# MOD_PWR_SW_CHM.net
KiCad netlist of a schematic drawn in Altium Designer
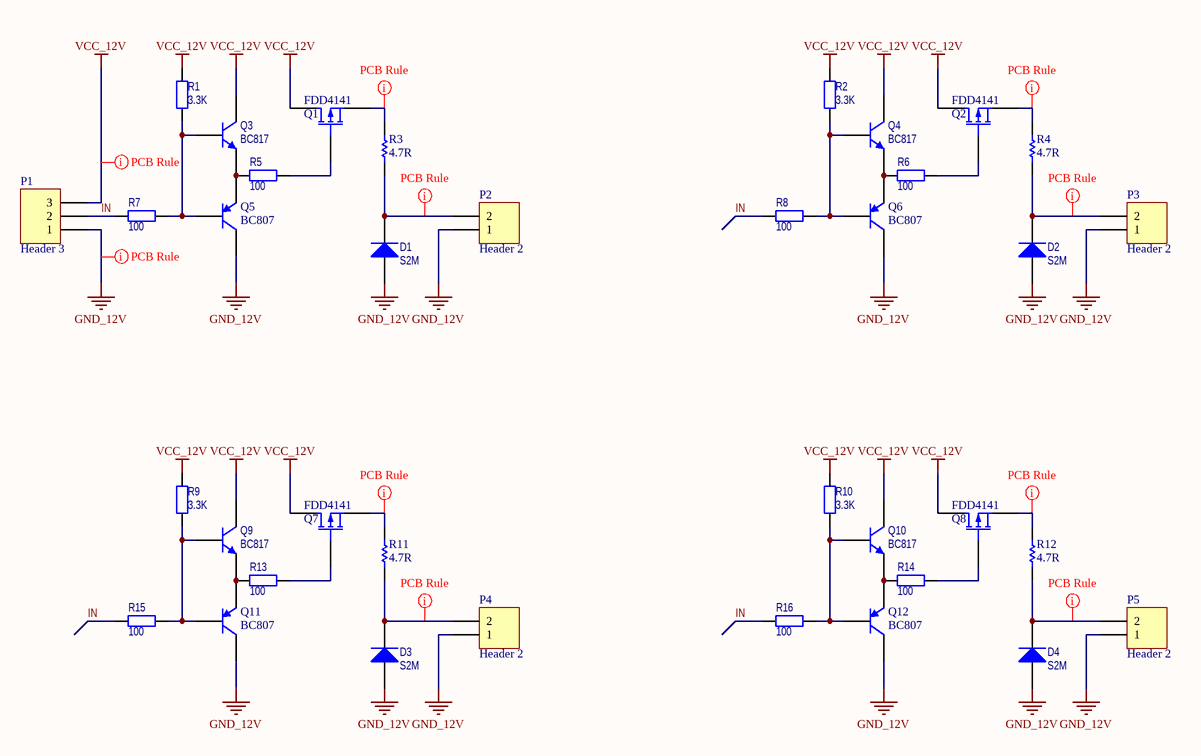
[diagram p0: MOD_PWR_SW_CHM.SchDoc]

(export (version "E")
  (design (tool "Eeschema 10.0.6"))
  (components
    (comp (ref "D1")
      (value "S2M")
      (footprint "SMB")
      (description "Default Diode")
      (fields (field (name "PUBLISHER") "Altium Limited"))
      (libsource (lib "Miscellaneous Devices") (part "Diode"))
    )
    (comp (ref "D2")
      (value "S2M")
      (footprint "SMB")
      (description "Default Diode")
      (fields (field (name "PUBLISHER") "Altium Limited"))
      (libsource (lib "Miscellaneous Devices") (part "Diode"))
    )
    (comp (ref "D3")
      (value "S2M")
      (footprint "SMB")
      (description "Default Diode")
      (fields (field (name "PUBLISHER") "Altium Limited"))
      (libsource (lib "Miscellaneous Devices") (part "Diode"))
    )
    (comp (ref "D4")
      (value "S2M")
      (footprint "SMB")
      (description "Default Diode")
      (fields (field (name "PUBLISHER") "Altium Limited"))
      (libsource (lib "Miscellaneous Devices") (part "Diode"))
    )
    (comp (ref "P1")
      (value "Header 3")
      (footprint "HDR1X3")
      (description "Header, 3-Pin")
      (fields (field (name "PUBLISHER") "Altium Limited"))
      (libsource (lib "Miscellaneous Connectors") (part "Header 3"))
    )
    (comp (ref "P2")
      (value "Header 2")
      (footprint "DG390-5.0:PCBComponent_1")
      (description "Header, 2-Pin")
      (fields (field (name "PUBLISHER") "Altium Limited"))
      (libsource (lib "Miscellaneous Connectors") (part "Header 2"))
    )
    (comp (ref "P3")
      (value "Header 2")
      (footprint "DG390-5.0:PCBComponent_1")
      (description "Header, 2-Pin")
      (fields (field (name "PUBLISHER") "Altium Limited"))
      (libsource (lib "Miscellaneous Connectors") (part "Header 2"))
    )
    (comp (ref "P4")
      (value "Header 2")
      (footprint "DG390-5.0:PCBComponent_1")
      (description "Header, 2-Pin")
      (fields (field (name "PUBLISHER") "Altium Limited"))
      (libsource (lib "Miscellaneous Connectors") (part "Header 2"))
    )
    (comp (ref "P5")
      (value "Header 2")
      (footprint "DG390-5.0:PCBComponent_1")
      (description "Header, 2-Pin")
      (fields (field (name "PUBLISHER") "Altium Limited"))
      (libsource (lib "Miscellaneous Connectors") (part "Header 2"))
    )
    (comp (ref "Q1")
      (value "FDD4141")
      (footprint "TO-252")
      (description "P-Channel MOSFET")
      (fields (field (name "PUBLISHER") "Altium Limited"))
      (libsource (lib "Miscellaneous Devices") (part "MOSFET-P"))
    )
    (comp (ref "Q2")
      (value "FDD4141")
      (footprint "TO-252")
      (description "P-Channel MOSFET")
      (fields (field (name "PUBLISHER") "Altium Limited"))
      (libsource (lib "Miscellaneous Devices") (part "MOSFET-P"))
    )
    (comp (ref "Q3")
      (value "BC817")
      (footprint "SOT23_M")
      (description "NPN Bipolar Transistor")
      (fields (field (name "PUBLISHER") "Altium Limited"))
      (libsource (lib "Miscellaneous Devices") (part "QNPN"))
    )
    (comp (ref "Q4")
      (value "BC817")
      (footprint "SOT23_M")
      (description "NPN Bipolar Transistor")
      (fields (field (name "PUBLISHER") "Altium Limited"))
      (libsource (lib "Miscellaneous Devices") (part "QNPN"))
    )
    (comp (ref "Q5")
      (value "BC807")
      (footprint "SOT23_M")
      (description "PNP General Purpose Amplifier")
      (fields (field (name "PUBLISHER") "Altium Limited"))
      (libsource (lib "Miscellaneous Devices") (part "2N3906"))
    )
    (comp (ref "Q6")
      (value "BC807")
      (footprint "SOT23_M")
      (description "PNP General Purpose Amplifier")
      (fields (field (name "PUBLISHER") "Altium Limited"))
      (libsource (lib "Miscellaneous Devices") (part "2N3906"))
    )
    (comp (ref "Q7")
      (value "FDD4141")
      (footprint "TO-252")
      (description "P-Channel MOSFET")
      (fields (field (name "PUBLISHER") "Altium Limited"))
      (libsource (lib "Miscellaneous Devices") (part "MOSFET-P"))
    )
    (comp (ref "Q8")
      (value "FDD4141")
      (footprint "TO-252")
      (description "P-Channel MOSFET")
      (fields (field (name "PUBLISHER") "Altium Limited"))
      (libsource (lib "Miscellaneous Devices") (part "MOSFET-P"))
    )
    (comp (ref "Q9")
      (value "BC817")
      (footprint "SOT23_M")
      (description "NPN Bipolar Transistor")
      (fields (field (name "PUBLISHER") "Altium Limited"))
      (libsource (lib "Miscellaneous Devices") (part "QNPN"))
    )
    (comp (ref "Q10")
      (value "BC817")
      (footprint "SOT23_M")
      (description "NPN Bipolar Transistor")
      (fields (field (name "PUBLISHER") "Altium Limited"))
      (libsource (lib "Miscellaneous Devices") (part "QNPN"))
    )
    (comp (ref "Q11")
      (value "BC807")
      (footprint "SOT23_M")
      (description "PNP General Purpose Amplifier")
      (fields (field (name "PUBLISHER") "Altium Limited"))
      (libsource (lib "Miscellaneous Devices") (part "2N3906"))
    )
    (comp (ref "Q12")
      (value "BC807")
      (footprint "SOT23_M")
      (description "PNP General Purpose Amplifier")
      (fields (field (name "PUBLISHER") "Altium Limited"))
      (libsource (lib "Miscellaneous Devices") (part "2N3906"))
    )
    (comp (ref "R1")
      (value "3.3K")
      (footprint "6-0805_N")
      (description "Resistor")
      (fields (field (name "Comment") "Res2") (field (name "PUBLISHER") "Altium Limited"))
      (libsource (lib "Miscellaneous Devices") (part "Res2"))
    )
    (comp (ref "R2")
      (value "3.3K")
      (footprint "6-0805_N")
      (description "Resistor")
      (fields (field (name "Comment") "Res2") (field (name "PUBLISHER") "Altium Limited"))
      (libsource (lib "Miscellaneous Devices") (part "Res2"))
    )
    (comp (ref "R3")
      (value "4.7R")
      (footprint "RES10W:PCBComponent_1")
      (description "Resistor")
      (fields (field (name "Comment") "Res1") (field (name "PUBLISHER") "Altium Limited"))
      (libsource (lib "Miscellaneous Devices") (part "Res1"))
    )
    (comp (ref "R4")
      (value "4.7R")
      (footprint "RES10W:PCBComponent_1")
      (description "Resistor")
      (fields (field (name "Comment") "Res1") (field (name "PUBLISHER") "Altium Limited"))
      (libsource (lib "Miscellaneous Devices") (part "Res1"))
    )
    (comp (ref "R5")
      (value "100")
      (footprint "6-0805_N")
      (description "Resistor")
      (fields (field (name "Comment") "Res2") (field (name "PUBLISHER") "Altium Limited"))
      (libsource (lib "") (part "Res2_1"))
    )
    (comp (ref "R6")
      (value "100")
      (footprint "6-0805_N")
      (description "Resistor")
      (fields (field (name "Comment") "Res2") (field (name "PUBLISHER") "Altium Limited"))
      (libsource (lib "") (part "Res2_1"))
    )
    (comp (ref "R7")
      (value "100")
      (footprint "6-0805_N")
      (description "Resistor")
      (fields (field (name "Comment") "Res2") (field (name "PUBLISHER") "Altium Limited"))
      (libsource (lib "") (part "Res2_1"))
    )
    (comp (ref "R8")
      (value "100")
      (footprint "6-0805_N")
      (description "Resistor")
      (fields (field (name "Comment") "Res2") (field (name "PUBLISHER") "Altium Limited"))
      (libsource (lib "") (part "Res2_1"))
    )
    (comp (ref "R9")
      (value "3.3K")
      (footprint "6-0805_N")
      (description "Resistor")
      (fields (field (name "Comment") "Res2") (field (name "PUBLISHER") "Altium Limited"))
      (libsource (lib "Miscellaneous Devices") (part "Res2"))
    )
    (comp (ref "R10")
      (value "3.3K")
      (footprint "6-0805_N")
      (description "Resistor")
      (fields (field (name "Comment") "Res2") (field (name "PUBLISHER") "Altium Limited"))
      (libsource (lib "Miscellaneous Devices") (part "Res2"))
    )
    (comp (ref "R11")
      (value "4.7R")
      (footprint "RES10W:PCBComponent_1")
      (description "Resistor")
      (fields (field (name "Comment") "Res1") (field (name "PUBLISHER") "Altium Limited"))
      (libsource (lib "Miscellaneous Devices") (part "Res1"))
    )
    (comp (ref "R12")
      (value "4.7R")
      (footprint "RES10W:PCBComponent_1")
      (description "Resistor")
      (fields (field (name "Comment") "Res1") (field (name "PUBLISHER") "Altium Limited"))
      (libsource (lib "Miscellaneous Devices") (part "Res1"))
    )
    (comp (ref "R13")
      (value "100")
      (footprint "6-0805_N")
      (description "Resistor")
      (fields (field (name "Comment") "Res2") (field (name "PUBLISHER") "Altium Limited"))
      (libsource (lib "") (part "Res2_1"))
    )
    (comp (ref "R14")
      (value "100")
      (footprint "6-0805_N")
      (description "Resistor")
      (fields (field (name "Comment") "Res2") (field (name "PUBLISHER") "Altium Limited"))
      (libsource (lib "") (part "Res2_1"))
    )
    (comp (ref "R15")
      (value "100")
      (footprint "6-0805_N")
      (description "Resistor")
      (fields (field (name "Comment") "Res2") (field (name "PUBLISHER") "Altium Limited"))
      (libsource (lib "") (part "Res2_1"))
    )
    (comp (ref "R16")
      (value "100")
      (footprint "6-0805_N")
      (description "Resistor")
      (fields (field (name "Comment") "Res2") (field (name "PUBLISHER") "Altium Limited"))
      (libsource (lib "") (part "Res2_1"))
    )
  )
  (nets
    (net (code "1") (name "/IN") (class "Default")
      (node (ref "P1") (pin "2") (pinfunction "2_2") (pintype "passive"))
      (node (ref "R15") (pin "2") (pinfunction "2_2") (pintype "passive"))
      (node (ref "R16") (pin "2") (pinfunction "2_2") (pintype "passive"))
      (node (ref "R7") (pin "2") (pinfunction "2_2") (pintype "passive"))
      (node (ref "R8") (pin "2") (pinfunction "2_2") (pintype "passive"))
    )
    (net (code "2") (name "GND_12V") (class "Default")
      (node (ref "D1") (pin "1") (pinfunction "A_1") (pintype "passive"))
      (node (ref "D2") (pin "1") (pinfunction "A_1") (pintype "passive"))
      (node (ref "D3") (pin "1") (pinfunction "A_1") (pintype "passive"))
      (node (ref "D4") (pin "1") (pinfunction "A_1") (pintype "passive"))
      (node (ref "P1") (pin "1") (pinfunction "1_1") (pintype "passive"))
      (node (ref "P2") (pin "1") (pinfunction "1_1") (pintype "passive"))
      (node (ref "P3") (pin "1") (pinfunction "1_1") (pintype "passive"))
      (node (ref "P4") (pin "1") (pinfunction "1_1") (pintype "passive"))
      (node (ref "P5") (pin "1") (pinfunction "1_1") (pintype "passive"))
      (node (ref "Q11") (pin "3") (pinfunction "C_3") (pintype "passive"))
      (node (ref "Q12") (pin "3") (pinfunction "C_3") (pintype "passive"))
      (node (ref "Q5") (pin "3") (pinfunction "C_3") (pintype "passive"))
      (node (ref "Q6") (pin "3") (pinfunction "C_3") (pintype "passive"))
    )
    (net (code "3") (name "Net-(D1-K)") (class "Default")
      (node (ref "D1") (pin "2") (pinfunction "K_2") (pintype "passive"))
      (node (ref "P2") (pin "2") (pinfunction "2_2") (pintype "passive"))
      (node (ref "R3") (pin "1") (pinfunction "1_1") (pintype "passive"))
    )
    (net (code "4") (name "Net-(D2-K)") (class "Default")
      (node (ref "D2") (pin "2") (pinfunction "K_2") (pintype "passive"))
      (node (ref "P3") (pin "2") (pinfunction "2_2") (pintype "passive"))
      (node (ref "R4") (pin "1") (pinfunction "1_1") (pintype "passive"))
    )
    (net (code "5") (name "Net-(D3-K)") (class "Default")
      (node (ref "D3") (pin "2") (pinfunction "K_2") (pintype "passive"))
      (node (ref "P4") (pin "2") (pinfunction "2_2") (pintype "passive"))
      (node (ref "R11") (pin "1") (pinfunction "1_1") (pintype "passive"))
    )
    (net (code "6") (name "Net-(D4-K)") (class "Default")
      (node (ref "D4") (pin "2") (pinfunction "K_2") (pintype "passive"))
      (node (ref "P5") (pin "2") (pinfunction "2_2") (pintype "passive"))
      (node (ref "R12") (pin "1") (pinfunction "1_1") (pintype "passive"))
    )
    (net (code "7") (name "Net-(Q1-G)") (class "Default")
      (node (ref "Q1") (pin "2") (pinfunction "G_2") (pintype "passive"))
      (node (ref "R5") (pin "1") (pinfunction "1_1") (pintype "passive"))
    )
    (net (code "8") (name "Net-(Q1-S)") (class "Default")
      (node (ref "Q1") (pin "3") (pinfunction "S_3") (pintype "passive"))
      (node (ref "R3") (pin "2") (pinfunction "2_2") (pintype "passive"))
    )
    (net (code "9") (name "Net-(Q2-G)") (class "Default")
      (node (ref "Q2") (pin "2") (pinfunction "G_2") (pintype "passive"))
      (node (ref "R6") (pin "1") (pinfunction "1_1") (pintype "passive"))
    )
    (net (code "10") (name "Net-(Q2-S)") (class "Default")
      (node (ref "Q2") (pin "3") (pinfunction "S_3") (pintype "passive"))
      (node (ref "R4") (pin "2") (pinfunction "2_2") (pintype "passive"))
    )
    (net (code "11") (name "Net-(Q3-B)") (class "Default")
      (node (ref "Q3") (pin "2") (pinfunction "B_2") (pintype "passive"))
      (node (ref "Q5") (pin "2") (pinfunction "B_2") (pintype "passive"))
      (node (ref "R1") (pin "2") (pinfunction "2_2") (pintype "passive"))
      (node (ref "R7") (pin "1") (pinfunction "1_1") (pintype "passive"))
    )
    (net (code "12") (name "Net-(Q3-E)") (class "Default")
      (node (ref "Q3") (pin "3") (pinfunction "E_3") (pintype "passive"))
      (node (ref "Q5") (pin "1") (pinfunction "E_1") (pintype "passive"))
      (node (ref "R5") (pin "2") (pinfunction "2_2") (pintype "passive"))
    )
    (net (code "13") (name "Net-(Q4-B)") (class "Default")
      (node (ref "Q4") (pin "2") (pinfunction "B_2") (pintype "passive"))
      (node (ref "Q6") (pin "2") (pinfunction "B_2") (pintype "passive"))
      (node (ref "R2") (pin "2") (pinfunction "2_2") (pintype "passive"))
      (node (ref "R8") (pin "1") (pinfunction "1_1") (pintype "passive"))
    )
    (net (code "14") (name "Net-(Q4-E)") (class "Default")
      (node (ref "Q4") (pin "3") (pinfunction "E_3") (pintype "passive"))
      (node (ref "Q6") (pin "1") (pinfunction "E_1") (pintype "passive"))
      (node (ref "R6") (pin "2") (pinfunction "2_2") (pintype "passive"))
    )
    (net (code "15") (name "Net-(Q7-G)") (class "Default")
      (node (ref "Q7") (pin "2") (pinfunction "G_2") (pintype "passive"))
      (node (ref "R13") (pin "1") (pinfunction "1_1") (pintype "passive"))
    )
    (net (code "16") (name "Net-(Q7-S)") (class "Default")
      (node (ref "Q7") (pin "3") (pinfunction "S_3") (pintype "passive"))
      (node (ref "R11") (pin "2") (pinfunction "2_2") (pintype "passive"))
    )
    (net (code "17") (name "Net-(Q8-G)") (class "Default")
      (node (ref "Q8") (pin "2") (pinfunction "G_2") (pintype "passive"))
      (node (ref "R14") (pin "1") (pinfunction "1_1") (pintype "passive"))
    )
    (net (code "18") (name "Net-(Q8-S)") (class "Default")
      (node (ref "Q8") (pin "3") (pinfunction "S_3") (pintype "passive"))
      (node (ref "R12") (pin "2") (pinfunction "2_2") (pintype "passive"))
    )
    (net (code "19") (name "Net-(Q10-B)") (class "Default")
      (node (ref "Q10") (pin "2") (pinfunction "B_2") (pintype "passive"))
      (node (ref "Q12") (pin "2") (pinfunction "B_2") (pintype "passive"))
      (node (ref "R10") (pin "2") (pinfunction "2_2") (pintype "passive"))
      (node (ref "R16") (pin "1") (pinfunction "1_1") (pintype "passive"))
    )
    (net (code "20") (name "Net-(Q10-E)") (class "Default")
      (node (ref "Q10") (pin "3") (pinfunction "E_3") (pintype "passive"))
      (node (ref "Q12") (pin "1") (pinfunction "E_1") (pintype "passive"))
      (node (ref "R14") (pin "2") (pinfunction "2_2") (pintype "passive"))
    )
    (net (code "21") (name "Net-(Q11-B)") (class "Default")
      (node (ref "Q11") (pin "2") (pinfunction "B_2") (pintype "passive"))
      (node (ref "Q9") (pin "2") (pinfunction "B_2") (pintype "passive"))
      (node (ref "R15") (pin "1") (pinfunction "1_1") (pintype "passive"))
      (node (ref "R9") (pin "2") (pinfunction "2_2") (pintype "passive"))
    )
    (net (code "22") (name "Net-(Q11-E)") (class "Default")
      (node (ref "Q11") (pin "1") (pinfunction "E_1") (pintype "passive"))
      (node (ref "Q9") (pin "3") (pinfunction "E_3") (pintype "passive"))
      (node (ref "R13") (pin "2") (pinfunction "2_2") (pintype "passive"))
    )
    (net (code "23") (name "VCC_12V") (class "Default")
      (node (ref "P1") (pin "3") (pinfunction "3_3") (pintype "passive"))
      (node (ref "Q1") (pin "1") (pinfunction "D_1") (pintype "passive"))
      (node (ref "Q10") (pin "1") (pinfunction "C_1") (pintype "passive"))
      (node (ref "Q2") (pin "1") (pinfunction "D_1") (pintype "passive"))
      (node (ref "Q3") (pin "1") (pinfunction "C_1") (pintype "passive"))
      (node (ref "Q4") (pin "1") (pinfunction "C_1") (pintype "passive"))
      (node (ref "Q7") (pin "1") (pinfunction "D_1") (pintype "passive"))
      (node (ref "Q8") (pin "1") (pinfunction "D_1") (pintype "passive"))
      (node (ref "Q9") (pin "1") (pinfunction "C_1") (pintype "passive"))
      (node (ref "R1") (pin "1") (pinfunction "1_1") (pintype "passive"))
      (node (ref "R10") (pin "1") (pinfunction "1_1") (pintype "passive"))
      (node (ref "R2") (pin "1") (pinfunction "1_1") (pintype "passive"))
      (node (ref "R9") (pin "1") (pinfunction "1_1") (pintype "passive"))
    )
  )
)
